# SpaceVNXBaseBoard.net
KiCad netlist of a schematic drawn in Altium Designer
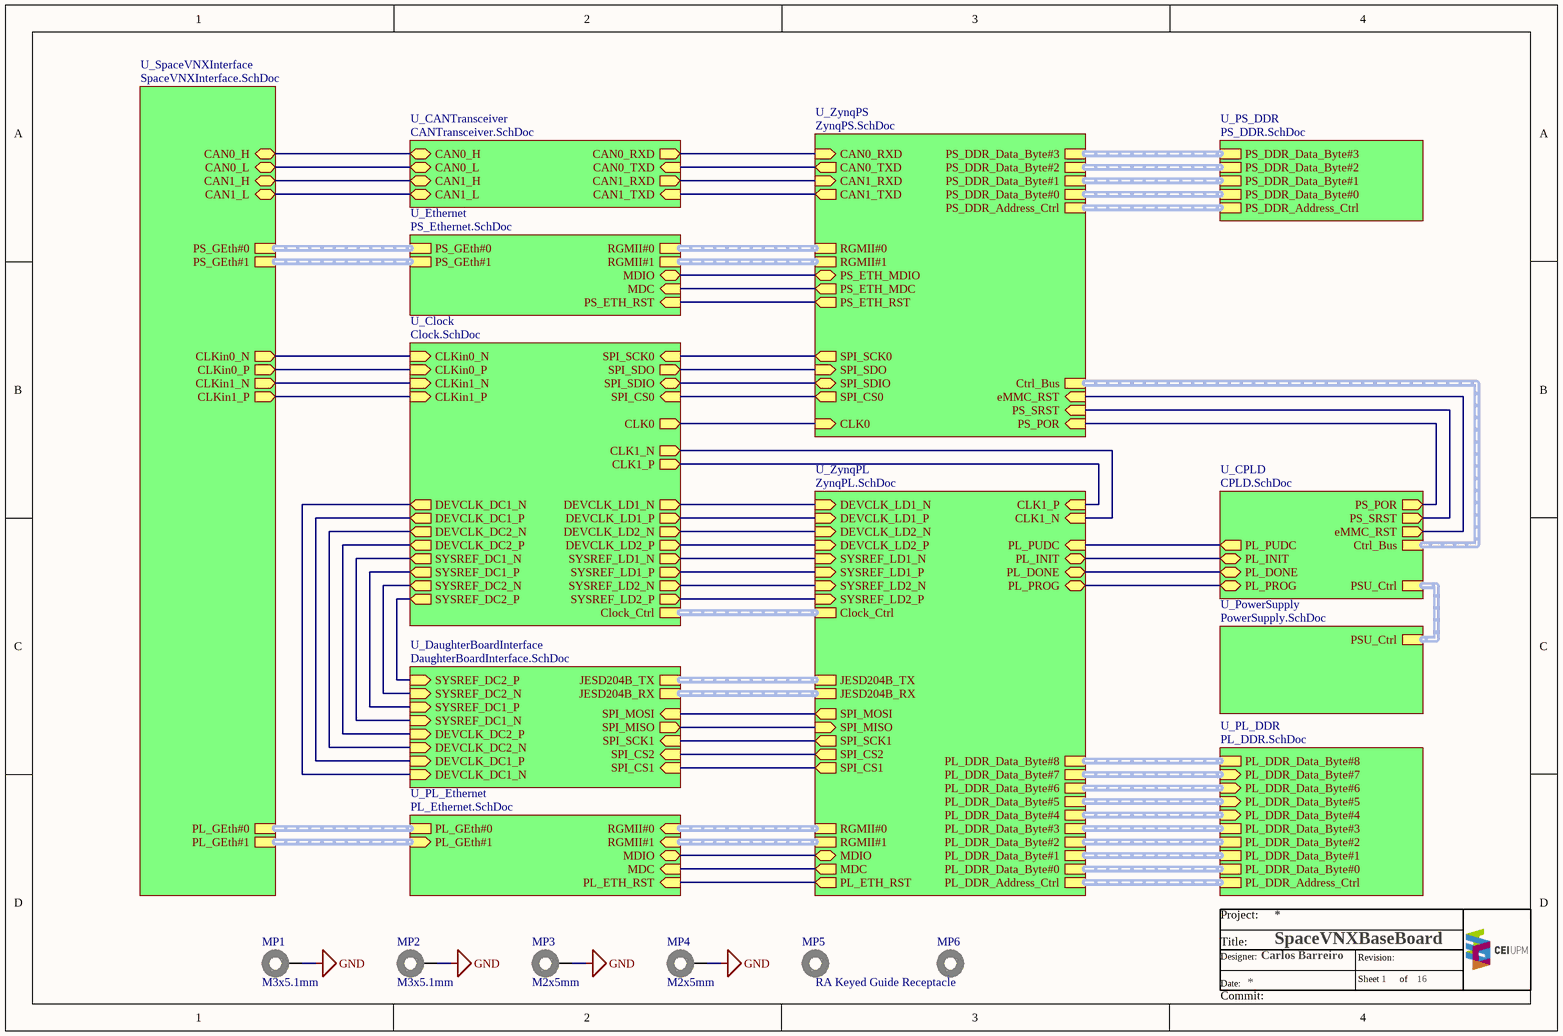
[diagram p0: SpaceVNXBaseBoard.SchDoc]

(export (version "E")
  (design (tool "Eeschema 10.0.6"))
  (components
    (comp (ref "MP1")
      (value "M3x5.1mm")
      (footprint "9775051360")
      (description "WA-SMSR SMT Steel Spacer Reverse with internal Thread M3, Length 5.1mm")
      (fields
        (field (name "MANUFACTURER PART NUMBER") "9775051360")
        (field (name "MANUFACTURER") "Wurth Elektronik")
      )
      (libsource (lib "SpaceVNX") (part "9775051360"))
    )
    (comp (ref "MP2")
      (value "M3x5.1mm")
      (footprint "9775051360")
      (description "WA-SMSR SMT Steel Spacer Reverse with internal Thread M3, Length 5.1mm")
      (fields
        (field (name "MANUFACTURER PART NUMBER") "9775051360")
        (field (name "MANUFACTURER") "Wurth Elektronik")
      )
      (libsource (lib "SpaceVNX") (part "9775051360"))
    )
    (comp (ref "MP3")
      (value "M2x5mm")
      (footprint "9774050243")
      (description "WA-SMSI SMT Steel Spacer, internal Thread, OD 4.35mm, M2x5mm")
      (fields
        (field (name "MANUFACTURER PART NUMBER") "9774050243")
        (field (name "MANUFACTURER") "Wurth Elektronik")
      )
      (libsource (lib "SpaceVNX") (part "9774050243"))
    )
    (comp (ref "MP4")
      (value "M2x5mm")
      (footprint "9774050243")
      (description "WA-SMSI SMT Steel Spacer, internal Thread, OD 4.35mm, M2x5mm")
      (fields
        (field (name "MANUFACTURER PART NUMBER") "9774050243")
        (field (name "MANUFACTURER") "Wurth Elektronik")
      )
      (libsource (lib "SpaceVNX") (part "9774050243"))
    )
    (comp (ref "MP5")
      (value "RA Keyed Guide Receptacle")
      (footprint "Guide Pin Receptacle")
      (description "Backplane Guide Hardware")
      (libsource (lib "SpaceVNX") (part "Vita74_Guide_Post"))
    )
    (comp (ref "MP6")
      (value "RA Keyed Guide Receptacle")
      (footprint "Guide Pin Receptacle")
      (description "Backplane Guide Hardware")
      (libsource (lib "SpaceVNX") (part "Vita74_Guide_Post"))
    )
  )
  (nets
    (net (code "82") (name "GND") (class "Default")
      (node (ref "MP1") (pin "1") (pinfunction "1_1") (pintype "passive"))
      (node (ref "MP2") (pin "1") (pinfunction "1_1") (pintype "passive"))
      (node (ref "MP3") (pin "1") (pinfunction "1_1") (pintype "passive"))
      (node (ref "MP4") (pin "1") (pinfunction "1_1") (pintype "passive"))
    )
  )
)
